# Top_level.net
KiCad netlist of a schematic drawn in Altium Designer
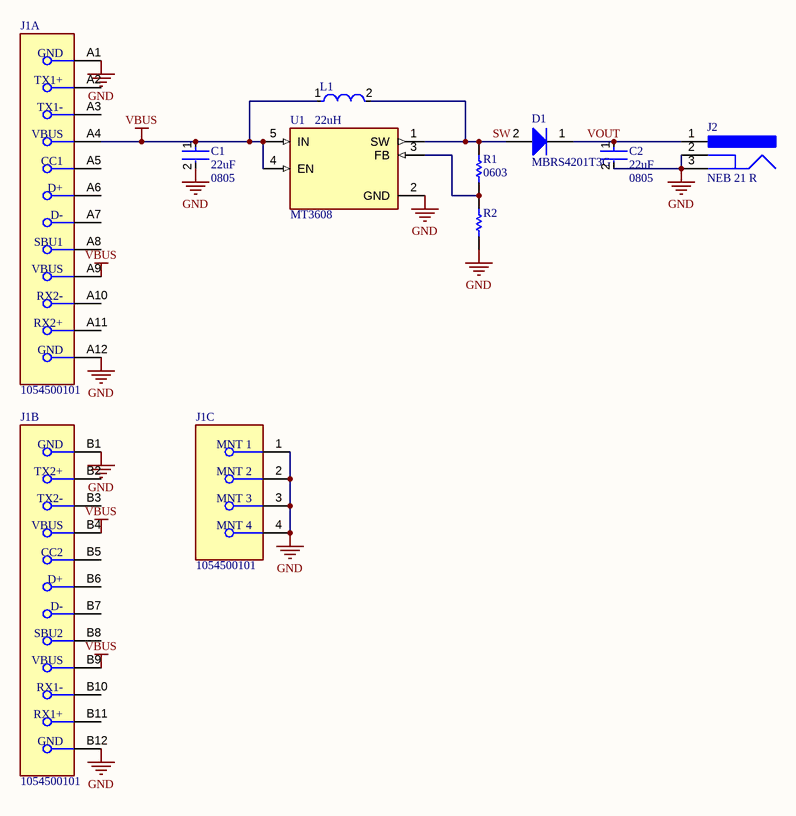
[diagram p0: Top level.SchDoc]

(export (version "E")
  (design (tool "Eeschema 10.0.6"))
  (components
    (comp (ref "C1")
      (value "GRM21BR60J226ME39L")
      (footprint "FP-GRM21B-0_15-MFG")
      (description "Chip Multilayer Ceramic Capacitors for General Purpose, 0805, 22uF, X5R, 15%, 20%, 6.3V")
      (fields
        (field (name "VOLTAGE") "6.3V")
        (field (name "TOLERANCE") "20%")
        (field (name "CAPACITANCE") "22uF")
        (field (name "CASE CODE (IMPERIAL)") "0805")
      )
      (libsource (lib "Altium Content Vault") (part "b4654b650e69147ec39a6b967a45e02"))
    )
    (comp (ref "C2")
      (value "GRM21BR60J226ME39L")
      (footprint "FP-GRM21B-0_15-MFG")
      (description "Chip Multilayer Ceramic Capacitors for General Purpose, 0805, 22uF, X5R, 15%, 20%, 6.3V")
      (fields
        (field (name "VOLTAGE") "6.3V")
        (field (name "TOLERANCE") "20%")
        (field (name "CAPACITANCE") "22uF")
        (field (name "CASE CODE (IMPERIAL)") "0805")
      )
      (libsource (lib "Altium Content Vault") (part "b4654b650e69147ec39a6b967a45e02"))
    )
    (comp (ref "D1")
      (value "MBRS4201T3G")
      (footprint "ONSC-SMC-2-403-03_V")
      (description "200 V, 4 A Schottky Fast Soft-Recovery Power Rectifier, 2-Pin SMC, Pb-Free, Tape and Reel")
      (fields (field (name "MANUFACTURER") "On Semiconductor"))
      (libsource (lib "Altium Content Vault") (part "ONSC-D-K1A2-2"))
    )
    (comp (ref "J1")
      (value "1054500101")
      (footprint "FP-1054500101-MFG")
      (description "CONN RCP USB3.1 TYPEC 24P SMD RA")
      (fields
        (field (name "MANUFACTURER") "Molex")
        (field (name "OCTOPART") "https://octopart.com/105450-0101-molex-68082325")
      )
      (libsource (lib "Altium Content Vault") (part "9808b19ecaf079fb99eed69f0495cd0"))
    )
    (comp (ref "J2")
      (value "NEB 21 R")
      (footprint "LUMB-NEB21R_V")
      (description "Jack Socket, Body 14.5 x 9 mm, Height 11 mm, -20 to 70 degC, 3-Pin THD, RoHS, Bulk")
      (fields (field (name "MANUFACTURER") "Lumberg"))
      (libsource (lib "Altium Content Vault") (part "JACK-2CD3-RN"))
    )
    (comp (ref "L1")
      (value "IHLP3232DZER220M11")
      (footprint "FP-IHLP-3232DZ-FP_2_413x5-MFG")
      (description "Commercial Inductors, Low DCR Series 22uH 4.3A 94.2mΩ 20%")
      (fields (field (name "INDUCTANCE") "22uH") (field (name "TOLERANCE") "20%"))
      (libsource (lib "Altium Content Vault") (part "725321dda6339637d4d059423bc1c3c"))
    )
    (comp (ref "R1")
      (value "ERJ3EKF1802V")
      (footprint "RESC1608X55X30LL15T15")
      (fields (field (name "MANUFACTURER") "Panasonic") (field (name "PACKAGE") "0603"))
      (libsource (lib "Altium Content Vault") (part "RES"))
    )
    (comp (ref "R2")
      (value "ERA3AEB162V")
      (footprint "RESC1608X55X30ML20T20")
      (fields (field (name "MANUFACTURER") "Panasonic"))
      (libsource (lib "Altium Content Vault") (part "RES"))
    )
    (comp (ref "U1")
      (value "MT3608")
      (footprint "MT3608:SOT95P280X145-6N")
      (description "High Efficiency 1.2MHz 2A Step Up Converter")
      (fields (field (name "MF") "{'manufacturer': u'Aerosemi Technology Co., Ltd'}"))
      (libsource (lib "*") (part "MT3608"))
    )
  )
  (nets
    (net (code "1") (name "/SW") (class "Default")
      (node (ref "D1") (pin "2") (pinfunction "A_2") (pintype "passive"))
      (node (ref "L1") (pin "2") (pinfunction "2_2") (pintype "passive"))
      (node (ref "R1") (pin "2") (pinfunction "2_2") (pintype "passive"))
      (node (ref "U1") (pin "1") (pinfunction "SW_1") (pintype "output"))
    )
    (net (code "2") (name "/VOUT") (class "Default")
      (node (ref "C2") (pin "1") (pinfunction "1_1") (pintype "passive"))
      (node (ref "D1") (pin "1") (pinfunction "K_1") (pintype "passive"))
      (node (ref "J2") (pin "1") (pinfunction "1_1") (pintype "passive"))
    )
    (net (code "3") (name "GND") (class "Default")
      (node (ref "C1") (pin "2") (pinfunction "2_2") (pintype "passive"))
      (node (ref "C2") (pin "2") (pinfunction "2_2") (pintype "passive"))
      (node (ref "J1") (pin "1") (pinfunction "MNT_1_1") (pintype "passive"))
      (node (ref "J1") (pin "2") (pinfunction "MNT_2_2") (pintype "passive"))
      (node (ref "J1") (pin "3") (pinfunction "MNT_3_3") (pintype "passive"))
      (node (ref "J1") (pin "4") (pinfunction "MNT_4_4") (pintype "passive"))
      (node (ref "J1") (pin "A1") (pinfunction "GND_A1") (pintype "passive"))
      (node (ref "J1") (pin "A12") (pinfunction "GND_A12") (pintype "passive"))
      (node (ref "J1") (pin "B1") (pinfunction "GND_B1") (pintype "passive"))
      (node (ref "J1") (pin "B12") (pinfunction "GND_B12") (pintype "passive"))
      (node (ref "J2") (pin "2") (pinfunction "2_2") (pintype "passive"))
      (node (ref "J2") (pin "3") (pinfunction "3_3") (pintype "passive"))
      (node (ref "R2") (pin "1") (pinfunction "1_1") (pintype "passive"))
      (node (ref "U1") (pin "2") (pinfunction "GND_2") (pintype "power_in"))
    )
    (net (code "4") (name "Net-(U1-FB)") (class "Default")
      (node (ref "R1") (pin "1") (pinfunction "1_1") (pintype "passive"))
      (node (ref "R2") (pin "2") (pinfunction "2_2") (pintype "passive"))
      (node (ref "U1") (pin "3") (pinfunction "FB_3") (pintype "input"))
    )
    (net (code "5") (name "VBUS") (class "Default")
      (node (ref "C1") (pin "1") (pinfunction "1_1") (pintype "passive"))
      (node (ref "J1") (pin "A4") (pinfunction "VBUS_A4") (pintype "passive"))
      (node (ref "J1") (pin "A9") (pinfunction "VBUS_A9") (pintype "passive"))
      (node (ref "J1") (pin "B4") (pinfunction "VBUS_B4") (pintype "passive"))
      (node (ref "J1") (pin "B9") (pinfunction "VBUS_B9") (pintype "passive"))
      (node (ref "L1") (pin "1") (pinfunction "1_1") (pintype "passive"))
      (node (ref "U1") (pin "4") (pinfunction "EN_4") (pintype "input"))
      (node (ref "U1") (pin "5") (pinfunction "IN_5") (pintype "input"))
    )
    (net (code "6") (name "unconnected-(J1A-CC1-PadA5)") (class "Default")
      (node (ref "J1") (pin "A5") (pinfunction "CC1_A5") (pintype "passive"))
    )
    (net (code "7") (name "unconnected-(J1A-D+-PadA6)") (class "Default")
      (node (ref "J1") (pin "A6") (pinfunction "D+_A6") (pintype "passive"))
    )
    (net (code "8") (name "unconnected-(J1A-D--PadA7)") (class "Default")
      (node (ref "J1") (pin "A7") (pinfunction "D-_A7") (pintype "passive"))
    )
    (net (code "9") (name "unconnected-(J1A-RX2+-PadA11)") (class "Default")
      (node (ref "J1") (pin "A11") (pinfunction "RX2+_A11") (pintype "passive"))
    )
    (net (code "10") (name "unconnected-(J1A-RX2--PadA10)") (class "Default")
      (node (ref "J1") (pin "A10") (pinfunction "RX2-_A10") (pintype "passive"))
    )
    (net (code "11") (name "unconnected-(J1A-SBU1-PadA8)") (class "Default")
      (node (ref "J1") (pin "A8") (pinfunction "SBU1_A8") (pintype "passive"))
    )
    (net (code "12") (name "unconnected-(J1A-TX1+-PadA2)") (class "Default")
      (node (ref "J1") (pin "A2") (pinfunction "TX1+_A2") (pintype "passive"))
    )
    (net (code "13") (name "unconnected-(J1A-TX1--PadA3)") (class "Default")
      (node (ref "J1") (pin "A3") (pinfunction "TX1-_A3") (pintype "passive"))
    )
    (net (code "14") (name "unconnected-(J1B-CC2-PadB5)") (class "Default")
      (node (ref "J1") (pin "B5") (pinfunction "CC2_B5") (pintype "passive"))
    )
    (net (code "15") (name "unconnected-(J1B-D+-PadB6)") (class "Default")
      (node (ref "J1") (pin "B6") (pinfunction "D+_B6") (pintype "passive"))
    )
    (net (code "16") (name "unconnected-(J1B-D--PadB7)") (class "Default")
      (node (ref "J1") (pin "B7") (pinfunction "D-_B7") (pintype "passive"))
    )
    (net (code "17") (name "unconnected-(J1B-RX1+-PadB11)") (class "Default")
      (node (ref "J1") (pin "B11") (pinfunction "RX1+_B11") (pintype "passive"))
    )
    (net (code "18") (name "unconnected-(J1B-RX1--PadB10)") (class "Default")
      (node (ref "J1") (pin "B10") (pinfunction "RX1-_B10") (pintype "passive"))
    )
    (net (code "19") (name "unconnected-(J1B-SBU2-PadB8)") (class "Default")
      (node (ref "J1") (pin "B8") (pinfunction "SBU2_B8") (pintype "passive"))
    )
    (net (code "20") (name "unconnected-(J1B-TX2+-PadB2)") (class "Default")
      (node (ref "J1") (pin "B2") (pinfunction "TX2+_B2") (pintype "passive"))
    )
    (net (code "21") (name "unconnected-(J1B-TX2--PadB3)") (class "Default")
      (node (ref "J1") (pin "B3") (pinfunction "TX2-_B3") (pintype "passive"))
    )
  )
)
